# Counter.net
KiCad netlist of a schematic drawn in Altium Designer
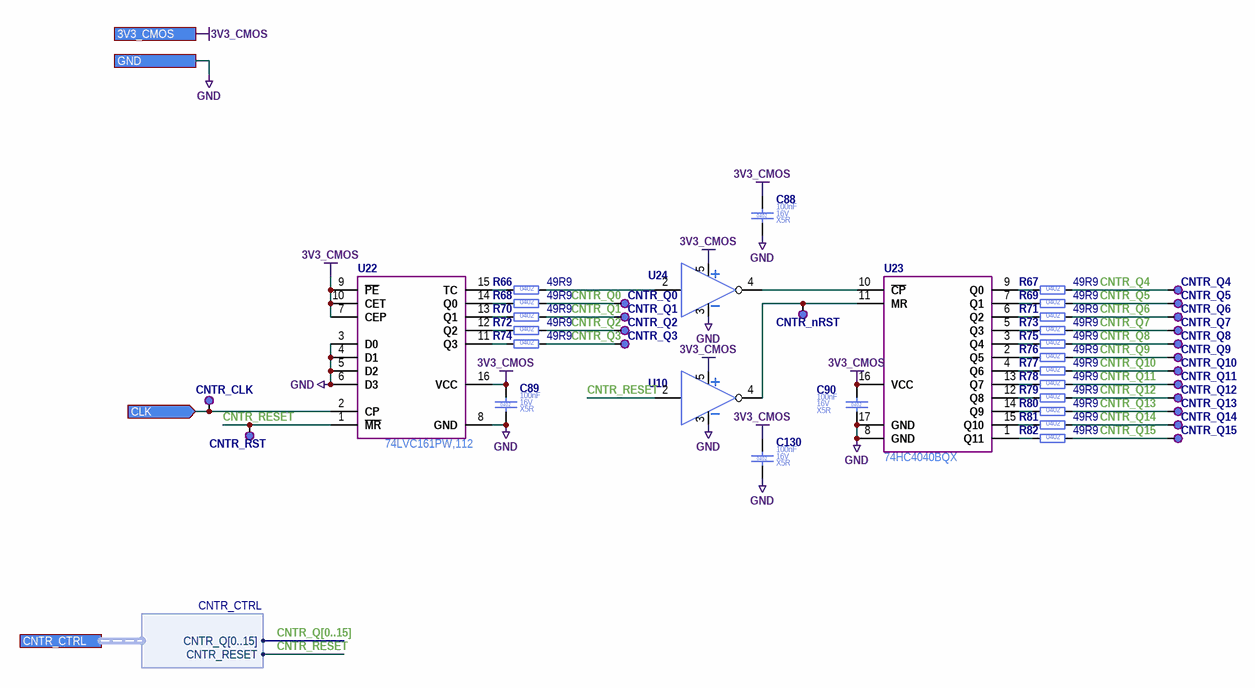
[diagram p0: Counter.SchDoc]

(export (version "E")
  (design (tool "Eeschema 10.0.6"))
  (components
    (comp (ref "C88")
      (value "C_100NF_16V_X5R_0402_10")
      (footprint "C_0402_1005")
      (description "Ceramic Capacitor")
      (fields
        (field (name "CASE/PACKAGE") "0402")
        (field (name "VOLTAGE RATING (DC)") "16V")
        (field (name "DIELECTRIC") "X5R")
        (field (name "CAPACITANCE") "100nF")
        (field (name "TOLERANCE") "10%")
        (field (name "MANUFACTURER PART NUMBER") "EMK105BJ104KV-F")
      )
      (libsource (lib "7Sigma") (part "C"))
    )
    (comp (ref "C89")
      (value "C_100NF_16V_X5R_0402_10")
      (footprint "C_0402_1005")
      (description "Ceramic Capacitor")
      (fields
        (field (name "CASE/PACKAGE") "0402")
        (field (name "VOLTAGE RATING (DC)") "16V")
        (field (name "DIELECTRIC") "X5R")
        (field (name "CAPACITANCE") "100nF")
        (field (name "TOLERANCE") "10%")
        (field (name "MANUFACTURER PART NUMBER") "EMK105BJ104KV-F")
      )
      (libsource (lib "7Sigma") (part "C"))
    )
    (comp (ref "C90")
      (value "C_100NF_16V_X5R_0402_10")
      (footprint "C_0402_1005")
      (description "Ceramic Capacitor")
      (fields
        (field (name "CASE/PACKAGE") "0402")
        (field (name "VOLTAGE RATING (DC)") "16V")
        (field (name "DIELECTRIC") "X5R")
        (field (name "CAPACITANCE") "100nF")
        (field (name "TOLERANCE") "10%")
        (field (name "MANUFACTURER PART NUMBER") "EMK105BJ104KV-F")
      )
      (libsource (lib "7Sigma") (part "C"))
    )
    (comp (ref "C130")
      (value "C_100NF_16V_X5R_0402_10")
      (footprint "C_0402_1005")
      (description "Ceramic Capacitor")
      (fields
        (field (name "CASE/PACKAGE") "0402")
        (field (name "VOLTAGE RATING (DC)") "16V")
        (field (name "DIELECTRIC") "X5R")
        (field (name "CAPACITANCE") "100nF")
        (field (name "TOLERANCE") "10%")
        (field (name "MANUFACTURER PART NUMBER") "EMK105BJ104KV-F")
      )
      (libsource (lib "7Sigma") (part "C"))
    )
    (comp (ref "CNTR_CLK")
      (value "TP_PAD_1.3MM")
      (footprint "TP_PAD_1.3MM")
      (description "Testpoint SMD 1.3mm")
      (libsource (lib "7Sigma") (part "TESTPOINT"))
    )
    (comp (ref "CNTR_nRST")
      (value "TP_PAD_1.3MM")
      (footprint "TP_PAD_1.3MM")
      (description "Testpoint SMD 1.3mm")
      (libsource (lib "7Sigma") (part "TESTPOINT"))
    )
    (comp (ref "CNTR_Q0")
      (value "TP_PAD_1.3MM")
      (footprint "TP_PAD_1.3MM")
      (description "Testpoint SMD 1.3mm")
      (libsource (lib "7Sigma") (part "TESTPOINT"))
    )
    (comp (ref "CNTR_Q1")
      (value "TP_PAD_1.3MM")
      (footprint "TP_PAD_1.3MM")
      (description "Testpoint SMD 1.3mm")
      (libsource (lib "7Sigma") (part "TESTPOINT"))
    )
    (comp (ref "CNTR_Q2")
      (value "TP_PAD_1.3MM")
      (footprint "TP_PAD_1.3MM")
      (description "Testpoint SMD 1.3mm")
      (libsource (lib "7Sigma") (part "TESTPOINT"))
    )
    (comp (ref "CNTR_Q3")
      (value "TP_PAD_1.3MM")
      (footprint "TP_PAD_1.3MM")
      (description "Testpoint SMD 1.3mm")
      (libsource (lib "7Sigma") (part "TESTPOINT"))
    )
    (comp (ref "CNTR_Q4")
      (value "TP_PAD_1.3MM")
      (footprint "TP_PAD_1.3MM")
      (description "Testpoint SMD 1.3mm")
      (libsource (lib "7Sigma") (part "TESTPOINT"))
    )
    (comp (ref "CNTR_Q5")
      (value "TP_PAD_1.3MM")
      (footprint "TP_PAD_1.3MM")
      (description "Testpoint SMD 1.3mm")
      (libsource (lib "7Sigma") (part "TESTPOINT"))
    )
    (comp (ref "CNTR_Q6")
      (value "TP_PAD_1.3MM")
      (footprint "TP_PAD_1.3MM")
      (description "Testpoint SMD 1.3mm")
      (libsource (lib "7Sigma") (part "TESTPOINT"))
    )
    (comp (ref "CNTR_Q7")
      (value "TP_PAD_1.3MM")
      (footprint "TP_PAD_1.3MM")
      (description "Testpoint SMD 1.3mm")
      (libsource (lib "7Sigma") (part "TESTPOINT"))
    )
    (comp (ref "CNTR_Q8")
      (value "TP_PAD_1.3MM")
      (footprint "TP_PAD_1.3MM")
      (description "Testpoint SMD 1.3mm")
      (libsource (lib "7Sigma") (part "TESTPOINT"))
    )
    (comp (ref "CNTR_Q9")
      (value "TP_PAD_1.3MM")
      (footprint "TP_PAD_1.3MM")
      (description "Testpoint SMD 1.3mm")
      (libsource (lib "7Sigma") (part "TESTPOINT"))
    )
    (comp (ref "CNTR_Q10")
      (value "TP_PAD_1.3MM")
      (footprint "TP_PAD_1.3MM")
      (description "Testpoint SMD 1.3mm")
      (libsource (lib "7Sigma") (part "TESTPOINT"))
    )
    (comp (ref "CNTR_Q11")
      (value "TP_PAD_1.3MM")
      (footprint "TP_PAD_1.3MM")
      (description "Testpoint SMD 1.3mm")
      (libsource (lib "7Sigma") (part "TESTPOINT"))
    )
    (comp (ref "CNTR_Q12")
      (value "TP_PAD_1.3MM")
      (footprint "TP_PAD_1.3MM")
      (description "Testpoint SMD 1.3mm")
      (libsource (lib "7Sigma") (part "TESTPOINT"))
    )
    (comp (ref "CNTR_Q13")
      (value "TP_PAD_1.3MM")
      (footprint "TP_PAD_1.3MM")
      (description "Testpoint SMD 1.3mm")
      (libsource (lib "7Sigma") (part "TESTPOINT"))
    )
    (comp (ref "CNTR_Q14")
      (value "TP_PAD_1.3MM")
      (footprint "TP_PAD_1.3MM")
      (description "Testpoint SMD 1.3mm")
      (libsource (lib "7Sigma") (part "TESTPOINT"))
    )
    (comp (ref "CNTR_Q15")
      (value "TP_PAD_1.3MM")
      (footprint "TP_PAD_1.3MM")
      (description "Testpoint SMD 1.3mm")
      (libsource (lib "7Sigma") (part "TESTPOINT"))
    )
    (comp (ref "CNTR_RST")
      (value "TP_PAD_1.3MM")
      (footprint "TP_PAD_1.3MM")
      (description "Testpoint SMD 1.3mm")
      (libsource (lib "7Sigma") (part "TESTPOINT"))
    )
    (comp (ref "R66")
      (value "R_49R9_0402_1")
      (footprint "R_0402_1005")
      (description "Thick Film Resistor")
      (fields
        (field (name "RESISTANCE") "49R9")
        (field (name "CASE/PACKAGE") "0402")
        (field (name "TOLERANCE") "1%")
        (field (name "MANUFACTURER") "Yageo")
      )
      (libsource (lib "7Sigma") (part "R"))
    )
    (comp (ref "R67")
      (value "R_49R9_0402_1")
      (footprint "R_0402_1005")
      (description "Thick Film Resistor")
      (fields
        (field (name "RESISTANCE") "49R9")
        (field (name "CASE/PACKAGE") "0402")
        (field (name "TOLERANCE") "1%")
        (field (name "MANUFACTURER") "Yageo")
      )
      (libsource (lib "7Sigma") (part "R"))
    )
    (comp (ref "R68")
      (value "R_49R9_0402_1")
      (footprint "R_0402_1005")
      (description "Thick Film Resistor")
      (fields
        (field (name "RESISTANCE") "49R9")
        (field (name "CASE/PACKAGE") "0402")
        (field (name "TOLERANCE") "1%")
        (field (name "MANUFACTURER") "Yageo")
      )
      (libsource (lib "7Sigma") (part "R"))
    )
    (comp (ref "R69")
      (value "R_49R9_0402_1")
      (footprint "R_0402_1005")
      (description "Thick Film Resistor")
      (fields
        (field (name "RESISTANCE") "49R9")
        (field (name "CASE/PACKAGE") "0402")
        (field (name "TOLERANCE") "1%")
        (field (name "MANUFACTURER") "Yageo")
      )
      (libsource (lib "7Sigma") (part "R"))
    )
    (comp (ref "R70")
      (value "R_49R9_0402_1")
      (footprint "R_0402_1005")
      (description "Thick Film Resistor")
      (fields
        (field (name "RESISTANCE") "49R9")
        (field (name "CASE/PACKAGE") "0402")
        (field (name "TOLERANCE") "1%")
        (field (name "MANUFACTURER") "Yageo")
      )
      (libsource (lib "7Sigma") (part "R"))
    )
    (comp (ref "R71")
      (value "R_49R9_0402_1")
      (footprint "R_0402_1005")
      (description "Thick Film Resistor")
      (fields
        (field (name "RESISTANCE") "49R9")
        (field (name "CASE/PACKAGE") "0402")
        (field (name "TOLERANCE") "1%")
        (field (name "MANUFACTURER") "Yageo")
      )
      (libsource (lib "7Sigma") (part "R"))
    )
    (comp (ref "R72")
      (value "R_49R9_0402_1")
      (footprint "R_0402_1005")
      (description "Thick Film Resistor")
      (fields
        (field (name "RESISTANCE") "49R9")
        (field (name "CASE/PACKAGE") "0402")
        (field (name "TOLERANCE") "1%")
        (field (name "MANUFACTURER") "Yageo")
      )
      (libsource (lib "7Sigma") (part "R"))
    )
    (comp (ref "R73")
      (value "R_49R9_0402_1")
      (footprint "R_0402_1005")
      (description "Thick Film Resistor")
      (fields
        (field (name "RESISTANCE") "49R9")
        (field (name "CASE/PACKAGE") "0402")
        (field (name "TOLERANCE") "1%")
        (field (name "MANUFACTURER") "Yageo")
      )
      (libsource (lib "7Sigma") (part "R"))
    )
    (comp (ref "R74")
      (value "R_49R9_0402_1")
      (footprint "R_0402_1005")
      (description "Thick Film Resistor")
      (fields
        (field (name "RESISTANCE") "49R9")
        (field (name "CASE/PACKAGE") "0402")
        (field (name "TOLERANCE") "1%")
        (field (name "MANUFACTURER") "Yageo")
      )
      (libsource (lib "7Sigma") (part "R"))
    )
    (comp (ref "R75")
      (value "R_49R9_0402_1")
      (footprint "R_0402_1005")
      (description "Thick Film Resistor")
      (fields
        (field (name "RESISTANCE") "49R9")
        (field (name "CASE/PACKAGE") "0402")
        (field (name "TOLERANCE") "1%")
        (field (name "MANUFACTURER") "Yageo")
      )
      (libsource (lib "7Sigma") (part "R"))
    )
    (comp (ref "R76")
      (value "R_49R9_0402_1")
      (footprint "R_0402_1005")
      (description "Thick Film Resistor")
      (fields
        (field (name "RESISTANCE") "49R9")
        (field (name "CASE/PACKAGE") "0402")
        (field (name "TOLERANCE") "1%")
        (field (name "MANUFACTURER") "Yageo")
      )
      (libsource (lib "7Sigma") (part "R"))
    )
    (comp (ref "R77")
      (value "R_49R9_0402_1")
      (footprint "R_0402_1005")
      (description "Thick Film Resistor")
      (fields
        (field (name "RESISTANCE") "49R9")
        (field (name "CASE/PACKAGE") "0402")
        (field (name "TOLERANCE") "1%")
        (field (name "MANUFACTURER") "Yageo")
      )
      (libsource (lib "7Sigma") (part "R"))
    )
    (comp (ref "R78")
      (value "R_49R9_0402_1")
      (footprint "R_0402_1005")
      (description "Thick Film Resistor")
      (fields
        (field (name "RESISTANCE") "49R9")
        (field (name "CASE/PACKAGE") "0402")
        (field (name "TOLERANCE") "1%")
        (field (name "MANUFACTURER") "Yageo")
      )
      (libsource (lib "7Sigma") (part "R"))
    )
    (comp (ref "R79")
      (value "R_49R9_0402_1")
      (footprint "R_0402_1005")
      (description "Thick Film Resistor")
      (fields
        (field (name "RESISTANCE") "49R9")
        (field (name "CASE/PACKAGE") "0402")
        (field (name "TOLERANCE") "1%")
        (field (name "MANUFACTURER") "Yageo")
      )
      (libsource (lib "7Sigma") (part "R"))
    )
    (comp (ref "R80")
      (value "R_49R9_0402_1")
      (footprint "R_0402_1005")
      (description "Thick Film Resistor")
      (fields
        (field (name "RESISTANCE") "49R9")
        (field (name "CASE/PACKAGE") "0402")
        (field (name "TOLERANCE") "1%")
        (field (name "MANUFACTURER") "Yageo")
      )
      (libsource (lib "7Sigma") (part "R"))
    )
    (comp (ref "R81")
      (value "R_49R9_0402_1")
      (footprint "R_0402_1005")
      (description "Thick Film Resistor")
      (fields
        (field (name "RESISTANCE") "49R9")
        (field (name "CASE/PACKAGE") "0402")
        (field (name "TOLERANCE") "1%")
        (field (name "MANUFACTURER") "Yageo")
      )
      (libsource (lib "7Sigma") (part "R"))
    )
    (comp (ref "R82")
      (value "R_49R9_0402_1")
      (footprint "R_0402_1005")
      (description "Thick Film Resistor")
      (fields
        (field (name "RESISTANCE") "49R9")
        (field (name "CASE/PACKAGE") "0402")
        (field (name "TOLERANCE") "1%")
        (field (name "MANUFACTURER") "Yageo")
      )
      (libsource (lib "7Sigma") (part "R"))
    )
    (comp (ref "U10")
      (value "SN74AHC1G04DBVR")
      (footprint "SOT23-5_SC74A_SOT753_M")
      (description "Inverters Single")
      (fields (field (name "MANUFACTURER") "Texas Instruments"))
      (libsource (lib "7Sigma") (part "SN74AHC1G04DBVR"))
    )
    (comp (ref "U22")
      (value "74LVC161PW,112")
      (footprint "TSOP65P640X120-16N")
      (description "4 bit Counter with preset")
      (fields
        (field (name "MANUFACTURER") "Nexperia")
        (field (name "MANUFACTURER PART NUMBER") "74LVC161PW,112")
      )
      (libsource (lib "7Sigma") (part "74LVC161PW"))
    )
    (comp (ref "U23")
      (value "74HC4040BQX")
      (footprint "QFN50P350X250X100_HS-17N")
      (description "12 bit binary ripple counter")
      (fields
        (field (name "MANUFACTURER PART NUMBER") "74HC4040BQX")
        (field (name "MANUFACTURER") "Nexperia")
      )
      (libsource (lib "7Sigma") (part "74HC4040BQX"))
    )
    (comp (ref "U24")
      (value "SN74AHC1G04DBVR")
      (footprint "SOT23-5_SC74A_SOT753_M")
      (description "Inverters Single")
      (fields (field (name "MANUFACTURER") "Texas Instruments"))
      (libsource (lib "7Sigma") (part "SN74AHC1G04DBVR"))
    )
  )
  (nets
    (net (code "2") (name "/CLK") (class "Default")
      (node (ref "CNTR_CLK") (pin "1") (pinfunction "TP_1") (pintype "passive"))
      (node (ref "U22") (pin "2") (pinfunction "CP_2") (pintype "passive"))
    )
    (net (code "3") (name "/CNTR_Q0") (class "Default")
      (node (ref "CNTR_Q0") (pin "1") (pinfunction "TP_1") (pintype "passive"))
      (node (ref "R68") (pin "2") (pinfunction "2_2") (pintype "passive"))
    )
    (net (code "4") (name "/CNTR_Q1") (class "Default")
      (node (ref "CNTR_Q1") (pin "1") (pinfunction "TP_1") (pintype "passive"))
      (node (ref "R70") (pin "2") (pinfunction "2_2") (pintype "passive"))
    )
    (net (code "5") (name "/CNTR_Q2") (class "Default")
      (node (ref "CNTR_Q2") (pin "1") (pinfunction "TP_1") (pintype "passive"))
      (node (ref "R72") (pin "2") (pinfunction "2_2") (pintype "passive"))
    )
    (net (code "6") (name "/CNTR_Q3") (class "Default")
      (node (ref "CNTR_Q3") (pin "1") (pinfunction "TP_1") (pintype "passive"))
      (node (ref "R74") (pin "2") (pinfunction "2_2") (pintype "passive"))
    )
    (net (code "7") (name "/CNTR_Q4") (class "Default")
      (node (ref "CNTR_Q4") (pin "1") (pinfunction "TP_1") (pintype "passive"))
      (node (ref "R67") (pin "2") (pinfunction "2_2") (pintype "passive"))
    )
    (net (code "8") (name "/CNTR_Q5") (class "Default")
      (node (ref "CNTR_Q5") (pin "1") (pinfunction "TP_1") (pintype "passive"))
      (node (ref "R69") (pin "2") (pinfunction "2_2") (pintype "passive"))
    )
    (net (code "9") (name "/CNTR_Q6") (class "Default")
      (node (ref "CNTR_Q6") (pin "1") (pinfunction "TP_1") (pintype "passive"))
      (node (ref "R71") (pin "2") (pinfunction "2_2") (pintype "passive"))
    )
    (net (code "10") (name "/CNTR_Q7") (class "Default")
      (node (ref "CNTR_Q7") (pin "1") (pinfunction "TP_1") (pintype "passive"))
      (node (ref "R73") (pin "2") (pinfunction "2_2") (pintype "passive"))
    )
    (net (code "11") (name "/CNTR_Q8") (class "Default")
      (node (ref "CNTR_Q8") (pin "1") (pinfunction "TP_1") (pintype "passive"))
      (node (ref "R75") (pin "2") (pinfunction "2_2") (pintype "passive"))
    )
    (net (code "12") (name "/CNTR_Q9") (class "Default")
      (node (ref "CNTR_Q9") (pin "1") (pinfunction "TP_1") (pintype "passive"))
      (node (ref "R76") (pin "2") (pinfunction "2_2") (pintype "passive"))
    )
    (net (code "13") (name "/CNTR_Q10") (class "Default")
      (node (ref "CNTR_Q10") (pin "1") (pinfunction "TP_1") (pintype "passive"))
      (node (ref "R77") (pin "2") (pinfunction "2_2") (pintype "passive"))
    )
    (net (code "14") (name "/CNTR_Q11") (class "Default")
      (node (ref "CNTR_Q11") (pin "1") (pinfunction "TP_1") (pintype "passive"))
      (node (ref "R78") (pin "2") (pinfunction "2_2") (pintype "passive"))
    )
    (net (code "15") (name "/CNTR_Q12") (class "Default")
      (node (ref "CNTR_Q12") (pin "1") (pinfunction "TP_1") (pintype "passive"))
      (node (ref "R79") (pin "2") (pinfunction "2_2") (pintype "passive"))
    )
    (net (code "16") (name "/CNTR_Q13") (class "Default")
      (node (ref "CNTR_Q13") (pin "1") (pinfunction "TP_1") (pintype "passive"))
      (node (ref "R80") (pin "2") (pinfunction "2_2") (pintype "passive"))
    )
    (net (code "17") (name "/CNTR_Q14") (class "Default")
      (node (ref "CNTR_Q14") (pin "1") (pinfunction "TP_1") (pintype "passive"))
      (node (ref "R81") (pin "2") (pinfunction "2_2") (pintype "passive"))
    )
    (net (code "18") (name "/CNTR_Q15") (class "Default")
      (node (ref "CNTR_Q15") (pin "1") (pinfunction "TP_1") (pintype "passive"))
      (node (ref "R82") (pin "2") (pinfunction "2_2") (pintype "passive"))
    )
    (net (code "20") (name "/CNTR_RESET") (class "Default")
      (node (ref "CNTR_RST") (pin "1") (pinfunction "TP_1") (pintype "passive"))
      (node (ref "U10") (pin "2") (pinfunction "2_2") (pintype "passive"))
      (node (ref "U22") (pin "1") (pinfunction "MR_1") (pintype "passive"))
    )
    (net (code "22") (name "3V3_CMOS") (class "Default")
      (node (ref "C130") (pin "1") (pinfunction "1_1") (pintype "passive"))
      (node (ref "C88") (pin "1") (pinfunction "1_1") (pintype "passive"))
      (node (ref "C89") (pin "1") (pinfunction "1_1") (pintype "passive"))
      (node (ref "C90") (pin "1") (pinfunction "1_1") (pintype "passive"))
      (node (ref "U10") (pin "5") (pinfunction "VCC_5") (pintype "passive"))
      (node (ref "U22") (pin "10") (pinfunction "CET_10") (pintype "passive"))
      (node (ref "U22") (pin "16") (pinfunction "VCC_16") (pintype "passive"))
      (node (ref "U22") (pin "7") (pinfunction "CEP_7") (pintype "passive"))
      (node (ref "U22") (pin "9") (pinfunction "PE_9") (pintype "passive"))
      (node (ref "U23") (pin "16") (pinfunction "VCC_16") (pintype "passive"))
      (node (ref "U24") (pin "5") (pinfunction "VCC_5") (pintype "passive"))
    )
    (net (code "23") (name "GND") (class "Default")
      (node (ref "C130") (pin "2") (pinfunction "2_2") (pintype "passive"))
      (node (ref "C88") (pin "2") (pinfunction "2_2") (pintype "passive"))
      (node (ref "C89") (pin "2") (pinfunction "2_2") (pintype "passive"))
      (node (ref "C90") (pin "2") (pinfunction "2_2") (pintype "passive"))
      (node (ref "U10") (pin "3") (pinfunction "GND_3") (pintype "passive"))
      (node (ref "U22") (pin "3") (pinfunction "D0_3") (pintype "passive"))
      (node (ref "U22") (pin "4") (pinfunction "D1_4") (pintype "passive"))
      (node (ref "U22") (pin "5") (pinfunction "D2_5") (pintype "passive"))
      (node (ref "U22") (pin "6") (pinfunction "D3_6") (pintype "passive"))
      (node (ref "U22") (pin "8") (pinfunction "GND_8") (pintype "passive"))
      (node (ref "U23") (pin "17") (pinfunction "GND_17") (pintype "passive"))
      (node (ref "U23") (pin "8") (pinfunction "GND_8") (pintype "passive"))
      (node (ref "U24") (pin "3") (pinfunction "GND_3") (pintype "passive"))
    )
    (net (code "24") (name "Net-(CNTR_nRST-TP)") (class "Default")
      (node (ref "CNTR_nRST") (pin "1") (pinfunction "TP_1") (pintype "passive"))
      (node (ref "U10") (pin "4") (pinfunction "OutY_4") (pintype "passive"))
      (node (ref "U23") (pin "11") (pinfunction "MR_11") (pintype "passive"))
    )
    (net (code "25") (name "Net-(R66-Pad2)") (class "Default")
      (node (ref "R66") (pin "2") (pinfunction "2_2") (pintype "passive"))
      (node (ref "U24") (pin "2") (pinfunction "2_2") (pintype "passive"))
    )
    (net (code "26") (name "Net-(U22-Q0)") (class "Default")
      (node (ref "R68") (pin "1") (pinfunction "1_1") (pintype "passive"))
      (node (ref "U22") (pin "14") (pinfunction "Q0_14") (pintype "passive"))
    )
    (net (code "27") (name "Net-(U22-Q1)") (class "Default")
      (node (ref "R70") (pin "1") (pinfunction "1_1") (pintype "passive"))
      (node (ref "U22") (pin "13") (pinfunction "Q1_13") (pintype "passive"))
    )
    (net (code "28") (name "Net-(U22-Q2)") (class "Default")
      (node (ref "R72") (pin "1") (pinfunction "1_1") (pintype "passive"))
      (node (ref "U22") (pin "12") (pinfunction "Q2_12") (pintype "passive"))
    )
    (net (code "29") (name "Net-(U22-Q3)") (class "Default")
      (node (ref "R74") (pin "1") (pinfunction "1_1") (pintype "passive"))
      (node (ref "U22") (pin "11") (pinfunction "Q3_11") (pintype "passive"))
    )
    (net (code "30") (name "Net-(U22-TC)") (class "Default")
      (node (ref "R66") (pin "1") (pinfunction "1_1") (pintype "passive"))
      (node (ref "U22") (pin "15") (pinfunction "TC_15") (pintype "passive"))
    )
    (net (code "31") (name "Net-(U23-CP)") (class "Default")
      (node (ref "U23") (pin "10") (pinfunction "CP_10") (pintype "passive"))
      (node (ref "U24") (pin "4") (pinfunction "OutY_4") (pintype "passive"))
    )
    (net (code "32") (name "Net-(U23-Q0)") (class "Default")
      (node (ref "R67") (pin "1") (pinfunction "1_1") (pintype "passive"))
      (node (ref "U23") (pin "9") (pinfunction "Q0_9") (pintype "passive"))
    )
    (net (code "33") (name "Net-(U23-Q1)") (class "Default")
      (node (ref "R69") (pin "1") (pinfunction "1_1") (pintype "passive"))
      (node (ref "U23") (pin "7") (pinfunction "Q1_7") (pintype "passive"))
    )
    (net (code "34") (name "Net-(U23-Q2)") (class "Default")
      (node (ref "R71") (pin "1") (pinfunction "1_1") (pintype "passive"))
      (node (ref "U23") (pin "6") (pinfunction "Q2_6") (pintype "passive"))
    )
    (net (code "35") (name "Net-(U23-Q3)") (class "Default")
      (node (ref "R73") (pin "1") (pinfunction "1_1") (pintype "passive"))
      (node (ref "U23") (pin "5") (pinfunction "Q3_5") (pintype "passive"))
    )
    (net (code "36") (name "Net-(U23-Q4)_1") (class "Default")
      (node (ref "R75") (pin "1") (pinfunction "1_1") (pintype "passive"))
      (node (ref "U23") (pin "3") (pinfunction "Q4_3") (pintype "passive"))
    )
    (net (code "37") (name "Net-(U23-Q5)") (class "Default")
      (node (ref "R76") (pin "1") (pinfunction "1_1") (pintype "passive"))
      (node (ref "U23") (pin "2") (pinfunction "Q5_2") (pintype "passive"))
    )
    (net (code "38") (name "Net-(U23-Q6)") (class "Default")
      (node (ref "R77") (pin "1") (pinfunction "1_1") (pintype "passive"))
      (node (ref "U23") (pin "4") (pinfunction "Q6_4") (pintype "passive"))
    )
    (net (code "39") (name "Net-(U23-Q7)") (class "Default")
      (node (ref "R78") (pin "1") (pinfunction "1_1") (pintype "passive"))
      (node (ref "U23") (pin "13") (pinfunction "Q7_13") (pintype "passive"))
    )
    (net (code "40") (name "Net-(U23-Q8)") (class "Default")
      (node (ref "R79") (pin "1") (pinfunction "1_1") (pintype "passive"))
      (node (ref "U23") (pin "12") (pinfunction "Q8_12") (pintype "passive"))
    )
    (net (code "41") (name "Net-(U23-Q9)") (class "Default")
      (node (ref "R80") (pin "1") (pinfunction "1_1") (pintype "passive"))
      (node (ref "U23") (pin "14") (pinfunction "Q9_14") (pintype "passive"))
    )
    (net (code "42") (name "Net-(U23-Q10)") (class "Default")
      (node (ref "R81") (pin "1") (pinfunction "1_1") (pintype "passive"))
      (node (ref "U23") (pin "15") (pinfunction "Q10_15") (pintype "passive"))
    )
    (net (code "43") (name "Net-(U23-Q11)") (class "Default")
      (node (ref "R82") (pin "1") (pinfunction "1_1") (pintype "passive"))
      (node (ref "U23") (pin "1") (pinfunction "Q11_1") (pintype "passive"))
    )
    (net (code "44") (name "unconnected-(U10-NC-Pad1)") (class "Default")
      (node (ref "U10") (pin "1") (pinfunction "NC_1") (pintype "passive"))
    )
    (net (code "45") (name "unconnected-(U23-Q4-Pad3)") (class "Default")
      (node (ref "U23") (pin "3") (pinfunction "Q4_3") (pintype "input"))
    )
    (net (code "46") (name "unconnected-(U24-NC-Pad1)") (class "Default")
      (node (ref "U24") (pin "1") (pinfunction "NC_1") (pintype "passive"))
    )
  )
)
